# schematic.net
KiCad netlist of a schematic drawn in Altium Designer
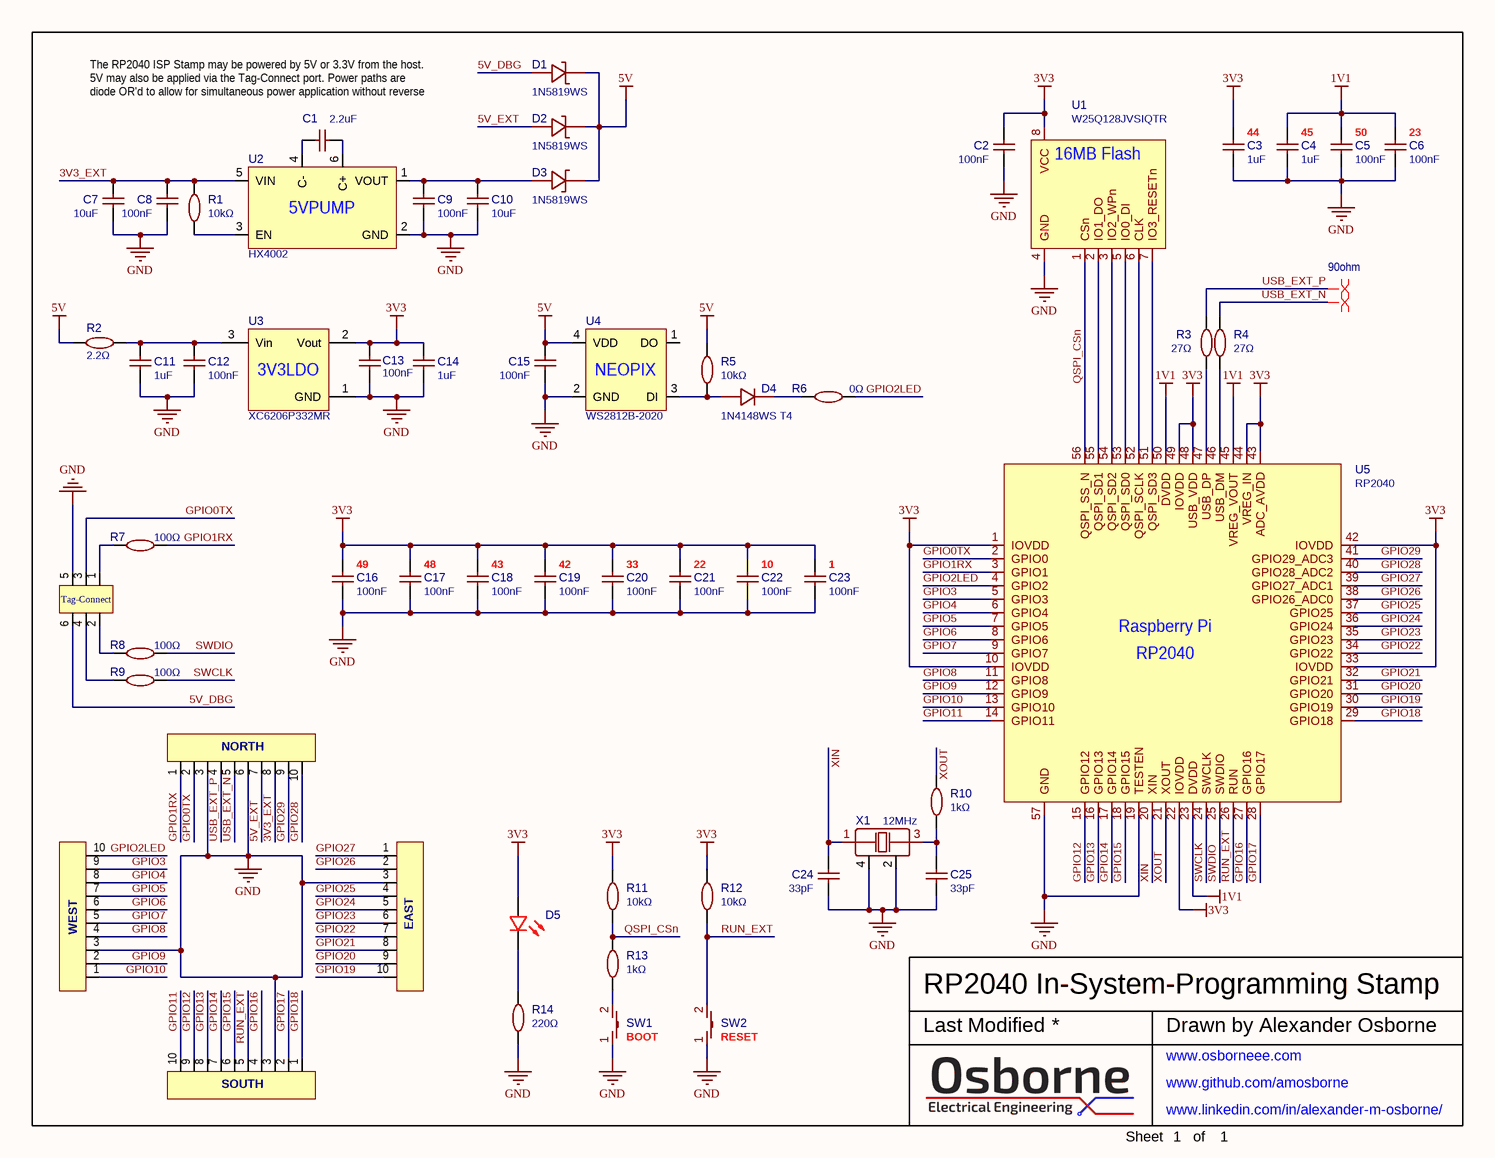
[diagram p0: schematic.SchDoc]

(export (version "E")
  (design (tool "Eeschema 10.0.6"))
  (components
    (comp (ref "C1")
      (value "2.2uF")
      (footprint "C0603")
      (description "16V 2.2uF X5R ±10% 0603  Multilayer Ceramic Capacitors MLCC - SMD/SMT ROHS")
      (fields
        (field (name "BOM_MANUFACTURER PART") "CL10A225KO8NNNC")
        (field (name "BOM_SUPPLIER PART") "C23630")
      )
      (libsource (lib "sch_library") (part "2.2uF"))
    )
    (comp (ref "C2")
      (value "100nF")
      (footprint "C0402")
      (description "16V 100nF X7R ±10% 0402  Multilayer Ceramic Capacitors MLCC - SMD/SMT ROHS")
      (fields
        (field (name "BOM_MANUFACTURER PART") "CL05B104KO5NNNC")
        (field (name "BOM_SUPPLIER PART") "C1525")
      )
      (libsource (lib "sch_library") (part "100nF"))
    )
    (comp (ref "C3")
      (value "1uF")
      (footprint "C0402")
      (description "25V 1uF X5R ±10% 0402  Multilayer Ceramic Capacitors MLCC - SMD/SMT ROHS")
      (fields
        (field (name "BOM_MANUFACTURER PART") "CL05A105KA5NQNC")
        (field (name "BOM_SUPPLIER PART") "C52923")
      )
      (libsource (lib "sch_library") (part "1uF"))
    )
    (comp (ref "C4")
      (value "1uF")
      (footprint "C0402")
      (description "25V 1uF X5R ±10% 0402  Multilayer Ceramic Capacitors MLCC - SMD/SMT ROHS")
      (fields
        (field (name "BOM_MANUFACTURER PART") "CL05A105KA5NQNC")
        (field (name "BOM_SUPPLIER PART") "C52923")
      )
      (libsource (lib "sch_library") (part "1uF"))
    )
    (comp (ref "C5")
      (value "100nF")
      (footprint "C0402")
      (description "16V 100nF X7R ±10% 0402  Multilayer Ceramic Capacitors MLCC - SMD/SMT ROHS")
      (fields
        (field (name "BOM_MANUFACTURER PART") "CL05B104KO5NNNC")
        (field (name "BOM_SUPPLIER PART") "C1525")
      )
      (libsource (lib "sch_library") (part "100nF"))
    )
    (comp (ref "C6")
      (value "100nF")
      (footprint "C0402")
      (description "16V 100nF X7R ±10% 0402  Multilayer Ceramic Capacitors MLCC - SMD/SMT ROHS")
      (fields
        (field (name "BOM_MANUFACTURER PART") "CL05B104KO5NNNC")
        (field (name "BOM_SUPPLIER PART") "C1525")
      )
      (libsource (lib "sch_library") (part "100nF"))
    )
    (comp (ref "C7")
      (value "10uF")
      (footprint "C0603")
      (description "X5R 25V ±20% 10uF 0603 Multilayer Ceramic Capacitors MLCC - SMD/SMT ROHS")
      (fields
        (field (name "BOM_MANUFACTURER PART") "CL10A106MA8NRNC")
        (field (name "BOM_SUPPLIER PART") "C96446")
      )
      (libsource (lib "sch_library") (part "10uF"))
    )
    (comp (ref "C8")
      (value "100nF")
      (footprint "C0402")
      (description "16V 100nF X7R ±10% 0402  Multilayer Ceramic Capacitors MLCC - SMD/SMT ROHS")
      (fields
        (field (name "BOM_MANUFACTURER PART") "CL05B104KO5NNNC")
        (field (name "BOM_SUPPLIER PART") "C1525")
      )
      (libsource (lib "sch_library") (part "100nF"))
    )
    (comp (ref "C9")
      (value "100nF")
      (footprint "C0402")
      (description "16V 100nF X7R ±10% 0402  Multilayer Ceramic Capacitors MLCC - SMD/SMT ROHS")
      (fields
        (field (name "BOM_MANUFACTURER PART") "CL05B104KO5NNNC")
        (field (name "BOM_SUPPLIER PART") "C1525")
      )
      (libsource (lib "sch_library") (part "100nF"))
    )
    (comp (ref "C10")
      (value "10uF")
      (footprint "C0603")
      (description "X5R 25V ±20% 10uF 0603 Multilayer Ceramic Capacitors MLCC - SMD/SMT ROHS")
      (fields
        (field (name "BOM_MANUFACTURER PART") "CL10A106MA8NRNC")
        (field (name "BOM_SUPPLIER PART") "C96446")
      )
      (libsource (lib "sch_library") (part "10uF"))
    )
    (comp (ref "C11")
      (value "1uF")
      (footprint "C0402")
      (description "25V 1uF X5R ±10% 0402  Multilayer Ceramic Capacitors MLCC - SMD/SMT ROHS")
      (fields
        (field (name "BOM_MANUFACTURER PART") "CL05A105KA5NQNC")
        (field (name "BOM_SUPPLIER PART") "C52923")
      )
      (libsource (lib "sch_library") (part "1uF"))
    )
    (comp (ref "C12")
      (value "100nF")
      (footprint "C0402")
      (description "16V 100nF X7R ±10% 0402  Multilayer Ceramic Capacitors MLCC - SMD/SMT ROHS")
      (fields
        (field (name "BOM_MANUFACTURER PART") "CL05B104KO5NNNC")
        (field (name "BOM_SUPPLIER PART") "C1525")
      )
      (libsource (lib "sch_library") (part "100nF"))
    )
    (comp (ref "C13")
      (value "100nF")
      (footprint "C0402")
      (description "16V 100nF X7R ±10% 0402  Multilayer Ceramic Capacitors MLCC - SMD/SMT ROHS")
      (fields
        (field (name "BOM_MANUFACTURER PART") "CL05B104KO5NNNC")
        (field (name "BOM_SUPPLIER PART") "C1525")
      )
      (libsource (lib "sch_library") (part "100nF"))
    )
    (comp (ref "C14")
      (value "1uF")
      (footprint "C0402")
      (description "25V 1uF X5R ±10% 0402  Multilayer Ceramic Capacitors MLCC - SMD/SMT ROHS")
      (fields
        (field (name "BOM_MANUFACTURER PART") "CL05A105KA5NQNC")
        (field (name "BOM_SUPPLIER PART") "C52923")
      )
      (libsource (lib "sch_library") (part "1uF"))
    )
    (comp (ref "C15")
      (value "100nF")
      (footprint "C0402")
      (description "16V 100nF X7R ±10% 0402  Multilayer Ceramic Capacitors MLCC - SMD/SMT ROHS")
      (fields
        (field (name "BOM_MANUFACTURER PART") "CL05B104KO5NNNC")
        (field (name "BOM_SUPPLIER PART") "C1525")
      )
      (libsource (lib "sch_library") (part "100nF"))
    )
    (comp (ref "C16")
      (value "100nF")
      (footprint "C0402")
      (description "16V 100nF X7R ±10% 0402  Multilayer Ceramic Capacitors MLCC - SMD/SMT ROHS")
      (fields
        (field (name "BOM_MANUFACTURER PART") "CL05B104KO5NNNC")
        (field (name "BOM_SUPPLIER PART") "C1525")
      )
      (libsource (lib "sch_library") (part "100nF"))
    )
    (comp (ref "C17")
      (value "100nF")
      (footprint "C0402")
      (description "16V 100nF X7R ±10% 0402  Multilayer Ceramic Capacitors MLCC - SMD/SMT ROHS")
      (fields
        (field (name "BOM_MANUFACTURER PART") "CL05B104KO5NNNC")
        (field (name "BOM_SUPPLIER PART") "C1525")
      )
      (libsource (lib "sch_library") (part "100nF"))
    )
    (comp (ref "C18")
      (value "100nF")
      (footprint "C0402")
      (description "16V 100nF X7R ±10% 0402  Multilayer Ceramic Capacitors MLCC - SMD/SMT ROHS")
      (fields
        (field (name "BOM_MANUFACTURER PART") "CL05B104KO5NNNC")
        (field (name "BOM_SUPPLIER PART") "C1525")
      )
      (libsource (lib "sch_library") (part "100nF"))
    )
    (comp (ref "C19")
      (value "100nF")
      (footprint "C0402")
      (description "16V 100nF X7R ±10% 0402  Multilayer Ceramic Capacitors MLCC - SMD/SMT ROHS")
      (fields
        (field (name "BOM_MANUFACTURER PART") "CL05B104KO5NNNC")
        (field (name "BOM_SUPPLIER PART") "C1525")
      )
      (libsource (lib "sch_library") (part "100nF"))
    )
    (comp (ref "C20")
      (value "100nF")
      (footprint "C0402")
      (description "16V 100nF X7R ±10% 0402  Multilayer Ceramic Capacitors MLCC - SMD/SMT ROHS")
      (fields
        (field (name "BOM_MANUFACTURER PART") "CL05B104KO5NNNC")
        (field (name "BOM_SUPPLIER PART") "C1525")
      )
      (libsource (lib "sch_library") (part "100nF"))
    )
    (comp (ref "C21")
      (value "100nF")
      (footprint "C0402")
      (description "16V 100nF X7R ±10% 0402  Multilayer Ceramic Capacitors MLCC - SMD/SMT ROHS")
      (fields
        (field (name "BOM_MANUFACTURER PART") "CL05B104KO5NNNC")
        (field (name "BOM_SUPPLIER PART") "C1525")
      )
      (libsource (lib "sch_library") (part "100nF"))
    )
    (comp (ref "C22")
      (value "100nF")
      (footprint "C0402")
      (description "16V 100nF X7R ±10% 0402  Multilayer Ceramic Capacitors MLCC - SMD/SMT ROHS")
      (fields
        (field (name "BOM_MANUFACTURER PART") "CL05B104KO5NNNC")
        (field (name "BOM_SUPPLIER PART") "C1525")
      )
      (libsource (lib "sch_library") (part "100nF"))
    )
    (comp (ref "C23")
      (value "100nF")
      (footprint "C0402")
      (description "16V 100nF X7R ±10% 0402  Multilayer Ceramic Capacitors MLCC - SMD/SMT ROHS")
      (fields
        (field (name "BOM_MANUFACTURER PART") "CL05B104KO5NNNC")
        (field (name "BOM_SUPPLIER PART") "C1525")
      )
      (libsource (lib "sch_library") (part "100nF"))
    )
    (comp (ref "C24")
      (value "33pF")
      (footprint "C0402")
      (description "50V 33pF C0G ±5% 0402  Multilayer Ceramic Capacitors MLCC - SMD/SMT ROHS")
      (fields
        (field (name "BOM_MANUFACTURER PART") "0402CG330J500NT")
        (field (name "BOM_SUPPLIER PART") "C1562")
      )
      (libsource (lib "sch_library") (part "33pF"))
    )
    (comp (ref "C25")
      (value "33pF")
      (footprint "C0402")
      (description "50V 33pF C0G ±5% 0402  Multilayer Ceramic Capacitors MLCC - SMD/SMT ROHS")
      (fields
        (field (name "BOM_MANUFACTURER PART") "0402CG330J500NT")
        (field (name "BOM_SUPPLIER PART") "C1562")
      )
      (libsource (lib "sch_library") (part "33pF"))
    )
    (comp (ref "D1")
      (value "1N5819WS")
      (footprint "SOD-323_L1.8-W1.3-LS2.5-RD")
      (description "40V 600mV@1A 1A SOD-323  Schottky Barrier Diodes (SBD) ROHS")
      (fields (field (name "BOM_SUPPLIER PART") "C191023") (field (name "CONTRIBUTOR") "LCSC"))
      (libsource (lib "sch_library") (part "1N5819WS"))
    )
    (comp (ref "D2")
      (value "1N5819WS")
      (footprint "SOD-323_L1.8-W1.3-LS2.5-RD")
      (description "40V 600mV@1A 1A SOD-323  Schottky Barrier Diodes (SBD) ROHS")
      (fields (field (name "BOM_SUPPLIER PART") "C191023") (field (name "CONTRIBUTOR") "LCSC"))
      (libsource (lib "sch_library") (part "1N5819WS"))
    )
    (comp (ref "D3")
      (value "1N5819WS")
      (footprint "SOD-323_L1.8-W1.3-LS2.5-RD")
      (description "40V 600mV@1A 1A SOD-323  Schottky Barrier Diodes (SBD) ROHS")
      (fields (field (name "BOM_SUPPLIER PART") "C191023") (field (name "CONTRIBUTOR") "LCSC"))
      (libsource (lib "sch_library") (part "1N5819WS"))
    )
    (comp (ref "D4")
      (value "1N4148WS T4")
      (footprint "SOD-323_L1.8-W1.3-LS2.5-RD")
      (description "100V +150℃@(Tj) 200mW Single 1.25V@150mA 4ns 1μA@75V 150mA SOD-323  Switching Diode ROHS")
      (fields (field (name "BOM_SUPPLIER PART") "C2128"))
      (libsource (lib "sch_library") (part "1N4148WS T4"))
    )
    (comp (ref "D5")
      (value "19-217/GHC-YR1S2/3T")
      (footprint "LED0603-R-RD")
      (fields (field (name "BOM_SUPPLIER PART") "C72043"))
      (libsource (lib "sch_library") (part "19-217/GHC-YR1S2/3T"))
    )
    (comp (ref "EAST")
      (value "STAMPEDGE")
      (footprint "CASTELLATIONS")
      (description "RP2040 ISP Stamp Castellations")
      (libsource (lib "") (part "STAMPEDGE_3"))
    )
    (comp (ref "J1")
      (value "TC2030-IDC-NL")
      (footprint "TC2030-IDC-NL")
      (description "Tag-Connect 6-Pin No Legs")
      (libsource (lib "sch_library") (part "TC2030-IDC-NL"))
    )
    (comp (ref "NORTH")
      (value "STAMPEDGE")
      (footprint "CASTELLATIONS")
      (description "RP2040 ISP Stamp Castellations")
      (libsource (lib "") (part "STAMPEDGE_1"))
    )
    (comp (ref "R1")
      (value "10kΩ")
      (footprint "R0402")
      (fields
        (field (name "BOM_MANUFACTURER PART") "0402WGF1002TCE")
        (field (name "BOM_SUPPLIER PART") "C25744")
      )
      (libsource (lib "sch_library") (part "10kΩ"))
    )
    (comp (ref "R2")
      (value "2.2Ω")
      (footprint "R0603")
      (fields
        (field (name "BOM_MANUFACTURER PART") "0603WAF220KT5E")
        (field (name "BOM_SUPPLIER PART") "C22939")
      )
      (libsource (lib "sch_library") (part "2.2Ω"))
    )
    (comp (ref "R3")
      (value "27Ω")
      (footprint "R0603")
      (fields
        (field (name "BOM_MANUFACTURER PART") "0603WAF270JT5E")
        (field (name "BOM_SUPPLIER PART") "C25190")
      )
      (libsource (lib "sch_library") (part "27Ω"))
    )
    (comp (ref "R4")
      (value "27Ω")
      (footprint "R0603")
      (fields
        (field (name "BOM_MANUFACTURER PART") "0603WAF270JT5E")
        (field (name "BOM_SUPPLIER PART") "C25190")
      )
      (libsource (lib "sch_library") (part "27Ω"))
    )
    (comp (ref "R5")
      (value "10kΩ")
      (footprint "R0402")
      (fields
        (field (name "BOM_MANUFACTURER PART") "0402WGF1002TCE")
        (field (name "BOM_SUPPLIER PART") "C25744")
      )
      (libsource (lib "sch_library") (part "10kΩ"))
    )
    (comp (ref "R6")
      (value "0Ω")
      (footprint "R0805")
      (fields
        (field (name "BOM_MANUFACTURER PART") "0805W8F0000T5E")
        (field (name "BOM_SUPPLIER PART") "C17477")
      )
      (libsource (lib "sch_library") (part "0Ω"))
    )
    (comp (ref "R7")
      (value "100Ω")
      (footprint "R0402")
      (fields
        (field (name "BOM_MANUFACTURER PART") "0402WGF1000TCE")
        (field (name "BOM_SUPPLIER PART") "C25076")
      )
      (libsource (lib "sch_library") (part "100Ω"))
    )
    (comp (ref "R8")
      (value "100Ω")
      (footprint "R0402")
      (fields
        (field (name "BOM_MANUFACTURER PART") "0402WGF1000TCE")
        (field (name "BOM_SUPPLIER PART") "C25076")
      )
      (libsource (lib "sch_library") (part "100Ω"))
    )
    (comp (ref "R9")
      (value "100Ω")
      (footprint "R0402")
      (fields
        (field (name "BOM_MANUFACTURER PART") "0402WGF1000TCE")
        (field (name "BOM_SUPPLIER PART") "C25076")
      )
      (libsource (lib "sch_library") (part "100Ω"))
    )
    (comp (ref "R10")
      (value "1kΩ")
      (footprint "R0402")
      (fields
        (field (name "BOM_MANUFACTURER PART") "0402WGF1001TCE")
        (field (name "BOM_SUPPLIER PART") "C11702")
      )
      (libsource (lib "sch_library") (part "1kΩ"))
    )
    (comp (ref "R11")
      (value "10kΩ")
      (footprint "R0402")
      (fields
        (field (name "BOM_MANUFACTURER PART") "0402WGF1002TCE")
        (field (name "BOM_SUPPLIER PART") "C25744")
      )
      (libsource (lib "sch_library") (part "10kΩ"))
    )
    (comp (ref "R12")
      (value "10kΩ")
      (footprint "R0402")
      (fields
        (field (name "BOM_MANUFACTURER PART") "0402WGF1002TCE")
        (field (name "BOM_SUPPLIER PART") "C25744")
      )
      (libsource (lib "sch_library") (part "10kΩ"))
    )
    (comp (ref "R13")
      (value "1kΩ")
      (footprint "R0402")
      (fields
        (field (name "BOM_MANUFACTURER PART") "0402WGF1001TCE")
        (field (name "BOM_SUPPLIER PART") "C11702")
      )
      (libsource (lib "sch_library") (part "1kΩ"))
    )
    (comp (ref "R14")
      (value "220Ω")
      (footprint "R0402")
      (fields
        (field (name "BOM_MANUFACTURER PART") "0402WGF2200TCE")
        (field (name "BOM_SUPPLIER PART") "C25091")
      )
      (libsource (lib "sch_library") (part "220Ω"))
    )
    (comp (ref "SOUTH")
      (value "STAMPEDGE")
      (footprint "CASTELLATIONS")
      (description "RP2040 ISP Stamp Castellations")
      (libsource (lib "sch_library") (part "STAMPEDGE"))
    )
    (comp (ref "SW1")
      (value "B3U-1000P")
      (footprint "KEY-SMD_B3U-1000PM")
      (description "2.5mm 1.6mm Round Button 50mA Brick nogging 3mm SPST 12V SMD,3x2.5x1.6mm  Tactile Switches ROHS")
      (fields (field (name "BOM_SUPPLIER PART") "C231329") (field (name "CONTRIBUTOR") "LCSC"))
      (libsource (lib "sch_library") (part "B3U-1000P"))
    )
    (comp (ref "SW2")
      (value "B3U-1000P")
      (footprint "KEY-SMD_B3U-1000PM")
      (description "2.5mm 1.6mm Round Button 50mA Brick nogging 3mm SPST 12V SMD,3x2.5x1.6mm  Tactile Switches ROHS")
      (fields (field (name "BOM_SUPPLIER PART") "C231329") (field (name "CONTRIBUTOR") "LCSC"))
      (libsource (lib "sch_library") (part "B3U-1000P"))
    )
    (comp (ref "U1")
      (value "W25Q128JVSIQTR")
      (footprint "SOIC-8_L5.3-W5.3-P1.27-LS8.0-BL")
      (description "SOIC-8_208mil  NOR FLASH ROHS")
      (fields (field (name "BOM_SUPPLIER PART") "C97521"))
      (libsource (lib "sch_library") (part "W25Q128JVSIQTR"))
    )
    (comp (ref "U2")
      (value "HX4002")
      (footprint "SOT-23-6_L2.9-W1.6-P0.95-LS2.8-BR")
      (description "NO Charge pump 1 5V 2.7V~5.5V 250mA 1.2MHz SOT-23-6  DC-DC Converters ROHS")
      (fields (field (name "BOM_SUPPLIER PART") "C172354") (field (name "CONTRIBUTOR") "LCSC"))
      (libsource (lib "sch_library") (part "HX4002"))
    )
    (comp (ref "U3")
      (value "XC6206P332MR")
      (footprint "SOT-23-3_L2.9-W1.6-P1.90-LS2.8-BR")
      (description "200mA 680mV@(100mA) Fixed 3.3V~3.3V Positive 1 6V SOT-23-3L  Linear Voltage Regulators (LDO) ROHS")
      (fields (field (name "BOM_SUPPLIER PART") "C5446"))
      (libsource (lib "sch_library") (part "XC6206P332MR"))
    )
    (comp (ref "U4")
      (value "WS2812B-2020")
      (footprint "LED-SMD_4P-L2.0-W2.0-TL_WS2812B-2020")
      (description "5mA 5.3V -25℃~+85℃ RGB SMD,2x2mm  Light Emitting Diodes (LED) ROHS")
      (fields (field (name "BOM_SUPPLIER PART") "C965555") (field (name "CONTRIBUTOR") "LCSC"))
      (libsource (lib "sch_library") (part "WS2812B-2020"))
    )
    (comp (ref "U5")
      (value "RP2040")
      (footprint "LQFN-56_L7.0-W7.0-P0.4-EP")
      (fields (field (name "BOM_SUPPLIER PART") "C2040") (field (name "CONTRIBUTOR") "LCSC"))
      (libsource (lib "sch_library") (part "RP2040"))
    )
    (comp (ref "WEST")
      (value "STAMPEDGE")
      (footprint "CASTELLATIONS")
      (description "RP2040 ISP Stamp Castellations")
      (libsource (lib "") (part "STAMPEDGE_2"))
    )
    (comp (ref "X1")
      (value "12MHz")
      (footprint "OSC-SMD_4P-L3.2-W2.5-BL")
      (description "12MHz SMD Crystal Resonator 20pF ±10ppm ±30ppm -40℃~+85℃ SMD3225-4P  Crystals ROHS")
      (fields
        (field (name "BOM_MANUFACTURER PART") "X322512MSB4SI")
        (field (name "BOM_SUPPLIER PART") "C9002")
      )
      (libsource (lib "sch_library") (part "12MHz"))
    )
  )
  (nets
    (net (code "1") (name "/3V3_EXT") (class "Default")
      (node (ref "C7") (pin "2") (pinfunction "2_2") (pintype "passive"))
      (node (ref "C8") (pin "2") (pinfunction "2_2") (pintype "passive"))
      (node (ref "NORTH") (pin "8") (pintype "passive"))
      (node (ref "R1") (pin "2") (pinfunction "2_2") (pintype "passive"))
      (node (ref "U2") (pin "5") (pinfunction "VIN_5") (pintype "passive"))
    )
    (net (code "2") (name "/5V_DBG") (class "Default")
      (node (ref "D1") (pin "2") (pinfunction "A_2") (pintype "passive"))
      (node (ref "J1") (pin "6") (pintype "passive"))
    )
    (net (code "3") (name "/5V_EXT") (class "Default")
      (node (ref "D2") (pin "2") (pinfunction "A_2") (pintype "passive"))
      (node (ref "NORTH") (pin "7") (pintype "passive"))
    )
    (net (code "4") (name "/GPIO0TX") (class "Default")
      (node (ref "J1") (pin "3") (pintype "passive"))
      (node (ref "NORTH") (pin "2") (pintype "passive"))
      (node (ref "U5") (pin "2") (pinfunction "GPIO0_2") (pintype "passive"))
    )
    (net (code "5") (name "/GPIO1RX") (class "Default")
      (node (ref "NORTH") (pin "1") (pintype "passive"))
      (node (ref "R7") (pin "1") (pinfunction "1_1") (pintype "passive"))
      (node (ref "U5") (pin "3") (pinfunction "GPIO1_3") (pintype "passive"))
    )
    (net (code "6") (name "/GPIO2LED") (class "Default")
      (node (ref "R6") (pin "2") (pinfunction "2_2") (pintype "passive"))
      (node (ref "U5") (pin "4") (pinfunction "GPIO2_4") (pintype "passive"))
      (node (ref "WEST") (pin "10") (pintype "passive"))
    )
    (net (code "7") (name "/GPIO3") (class "Default")
      (node (ref "U5") (pin "5") (pinfunction "GPIO3_5") (pintype "passive"))
      (node (ref "WEST") (pin "9") (pintype "passive"))
    )
    (net (code "8") (name "/GPIO4") (class "Default")
      (node (ref "U5") (pin "6") (pinfunction "GPIO4_6") (pintype "passive"))
      (node (ref "WEST") (pin "8") (pintype "passive"))
    )
    (net (code "9") (name "/GPIO5") (class "Default")
      (node (ref "U5") (pin "7") (pinfunction "GPIO5_7") (pintype "passive"))
      (node (ref "WEST") (pin "7") (pintype "passive"))
    )
    (net (code "10") (name "/GPIO6") (class "Default")
      (node (ref "U5") (pin "8") (pinfunction "GPIO6_8") (pintype "passive"))
      (node (ref "WEST") (pin "6") (pintype "passive"))
    )
    (net (code "11") (name "/GPIO7") (class "Default")
      (node (ref "U5") (pin "9") (pinfunction "GPIO7_9") (pintype "passive"))
      (node (ref "WEST") (pin "5") (pintype "passive"))
    )
    (net (code "12") (name "/GPIO8") (class "Default")
      (node (ref "U5") (pin "11") (pinfunction "GPIO8_11") (pintype "passive"))
      (node (ref "WEST") (pin "4") (pintype "passive"))
    )
    (net (code "13") (name "/GPIO9") (class "Default")
      (node (ref "U5") (pin "12") (pinfunction "GPIO9_12") (pintype "passive"))
      (node (ref "WEST") (pin "2") (pintype "passive"))
    )
    (net (code "14") (name "/GPIO10") (class "Default")
      (node (ref "U5") (pin "13") (pinfunction "GPIO10_13") (pintype "passive"))
      (node (ref "WEST") (pin "1") (pintype "passive"))
    )
    (net (code "15") (name "/GPIO11") (class "Default")
      (node (ref "SOUTH") (pin "10") (pintype "passive"))
      (node (ref "U5") (pin "14") (pinfunction "GPIO11_14") (pintype "passive"))
    )
    (net (code "16") (name "/GPIO12") (class "Default")
      (node (ref "SOUTH") (pin "9") (pintype "passive"))
      (node (ref "U5") (pin "15") (pinfunction "GPIO12_15") (pintype "passive"))
    )
    (net (code "17") (name "/GPIO13") (class "Default")
      (node (ref "SOUTH") (pin "8") (pintype "passive"))
      (node (ref "U5") (pin "16") (pinfunction "GPIO13_16") (pintype "passive"))
    )
    (net (code "18") (name "/GPIO14") (class "Default")
      (node (ref "SOUTH") (pin "7") (pintype "passive"))
      (node (ref "U5") (pin "17") (pinfunction "GPIO14_17") (pintype "passive"))
    )
    (net (code "19") (name "/GPIO15") (class "Default")
      (node (ref "SOUTH") (pin "6") (pintype "passive"))
      (node (ref "U5") (pin "18") (pinfunction "GPIO15_18") (pintype "passive"))
    )
    (net (code "20") (name "/GPIO16") (class "Default")
      (node (ref "SOUTH") (pin "4") (pintype "passive"))
      (node (ref "U5") (pin "27") (pinfunction "GPIO16_27") (pintype "passive"))
    )
    (net (code "21") (name "/GPIO17") (class "Default")
      (node (ref "SOUTH") (pin "2") (pintype "passive"))
      (node (ref "U5") (pin "28") (pinfunction "GPIO17_28") (pintype "passive"))
    )
    (net (code "22") (name "/GPIO18") (class "Default")
      (node (ref "SOUTH") (pin "1") (pintype "passive"))
      (node (ref "U5") (pin "29") (pinfunction "GPIO18_29") (pintype "passive"))
    )
    (net (code "23") (name "/GPIO19") (class "Default")
      (node (ref "EAST") (pin "10") (pintype "passive"))
      (node (ref "U5") (pin "30") (pinfunction "GPIO19_30") (pintype "passive"))
    )
    (net (code "24") (name "/GPIO20") (class "Default")
      (node (ref "EAST") (pin "9") (pintype "passive"))
      (node (ref "U5") (pin "31") (pinfunction "GPIO20_31") (pintype "passive"))
    )
    (net (code "25") (name "/GPIO21") (class "Default")
      (node (ref "EAST") (pin "8") (pintype "passive"))
      (node (ref "U5") (pin "32") (pinfunction "GPIO21_32") (pintype "passive"))
    )
    (net (code "26") (name "/GPIO22") (class "Default")
      (node (ref "EAST") (pin "7") (pintype "passive"))
      (node (ref "U5") (pin "34") (pinfunction "GPIO22_34") (pintype "passive"))
    )
    (net (code "27") (name "/GPIO23") (class "Default")
      (node (ref "EAST") (pin "6") (pintype "passive"))
      (node (ref "U5") (pin "35") (pinfunction "GPIO23_35") (pintype "passive"))
    )
    (net (code "28") (name "/GPIO24") (class "Default")
      (node (ref "EAST") (pin "5") (pintype "passive"))
      (node (ref "U5") (pin "36") (pinfunction "GPIO24_36") (pintype "passive"))
    )
    (net (code "29") (name "/GPIO25") (class "Default")
      (node (ref "EAST") (pin "4") (pintype "passive"))
      (node (ref "U5") (pin "37") (pinfunction "GPIO25_37") (pintype "passive"))
    )
    (net (code "30") (name "/GPIO26") (class "Default")
      (node (ref "EAST") (pin "2") (pintype "passive"))
      (node (ref "U5") (pin "38") (pinfunction "GPIO26_ADC0_38") (pintype "passive"))
    )
    (net (code "31") (name "/GPIO27") (class "Default")
      (node (ref "EAST") (pin "1") (pintype "passive"))
      (node (ref "U5") (pin "39") (pinfunction "GPIO27_ADC1_39") (pintype "passive"))
    )
    (net (code "32") (name "/GPIO28") (class "Default")
      (node (ref "NORTH") (pin "10") (pintype "passive"))
      (node (ref "U5") (pin "40") (pinfunction "GPIO28_ADC2_40") (pintype "passive"))
    )
    (net (code "33") (name "/GPIO29") (class "Default")
      (node (ref "NORTH") (pin "9") (pintype "passive"))
      (node (ref "U5") (pin "41") (pinfunction "GPIO29_ADC3_41") (pintype "passive"))
    )
    (net (code "34") (name "/QSPI_CSn") (class "Default")
      (node (ref "R11") (pin "1") (pinfunction "1_1") (pintype "passive"))
      (node (ref "R13") (pin "2") (pinfunction "2_2") (pintype "passive"))
      (node (ref "U1") (pin "1") (pinfunction "CSn_1") (pintype "passive"))
      (node (ref "U5") (pin "56") (pinfunction "QSPI_SS_N_56") (pintype "passive"))
    )
    (net (code "35") (name "/RUN_EXT") (class "Default")
      (node (ref "R12") (pin "1") (pinfunction "1_1") (pintype "passive"))
      (node (ref "SOUTH") (pin "5") (pintype "passive"))
      (node (ref "SW2") (pin "2") (pinfunction "2_2") (pintype "passive"))
      (node (ref "U5") (pin "26") (pinfunction "RUN_26") (pintype "passive"))
    )
    (net (code "36") (name "/SWCLK") (class "Default")
      (node (ref "R9") (pin "1") (pinfunction "1_1") (pintype "passive"))
      (node (ref "U5") (pin "24") (pinfunction "SWCLK_24") (pintype "passive"))
    )
    (net (code "37") (name "/SWDIO") (class "Default")
      (node (ref "R8") (pin "1") (pinfunction "1_1") (pintype "passive"))
      (node (ref "U5") (pin "25") (pinfunction "SWDIO_25") (pintype "passive"))
    )
    (net (code "38") (name "/USB_EXT_N") (class "Default")
      (node (ref "NORTH") (pin "5") (pintype "passive"))
      (node (ref "R4") (pin "2") (pinfunction "2_2") (pintype "passive"))
    )
    (net (code "39") (name "/USB_EXT_P") (class "Default")
      (node (ref "NORTH") (pin "4") (pintype "passive"))
      (node (ref "R3") (pin "2") (pinfunction "2_2") (pintype "passive"))
    )
    (net (code "40") (name "/XIN") (class "Default")
      (node (ref "C24") (pin "2") (pinfunction "2_2") (pintype "passive"))
      (node (ref "U5") (pin "20") (pinfunction "XIN_20") (pintype "passive"))
      (node (ref "X1") (pin "1") (pinfunction "OSC1_1") (pintype "passive"))
    )
    (net (code "41") (name "/XOUT") (class "Default")
      (node (ref "R10") (pin "1") (pinfunction "1_1") (pintype "passive"))
      (node (ref "U5") (pin "21") (pinfunction "XOUT_21") (pintype "passive"))
    )
    (net (code "42") (name "1V1") (class "Default")
      (node (ref "C4") (pin "2") (pinfunction "2_2") (pintype "passive"))
      (node (ref "C5") (pin "2") (pinfunction "2_2") (pintype "passive"))
      (node (ref "C6") (pin "2") (pinfunction "2_2") (pintype "passive"))
      (node (ref "U5") (pin "23") (pinfunction "DVDD_23") (pintype "passive"))
      (node (ref "U5") (pin "45") (pinfunction "VREG_VOUT_45") (pintype "passive"))
      (node (ref "U5") (pin "50") (pinfunction "DVDD_50") (pintype "passive"))
    )
    (net (code "43") (name "3V3") (class "Default")
      (node (ref "C13") (pin "2") (pinfunction "2_2") (pintype "passive"))
      (node (ref "C14") (pin "2") (pinfunction "2_2") (pintype "passive"))
      (node (ref "C16") (pin "2") (pinfunction "2_2") (pintype "passive"))
      (node (ref "C17") (pin "2") (pinfunction "2_2") (pintype "passive"))
      (node (ref "C18") (pin "2") (pinfunction "2_2") (pintype "passive"))
      (node (ref "C19") (pin "2") (pinfunction "2_2") (pintype "passive"))
      (node (ref "C2") (pin "2") (pinfunction "2_2") (pintype "passive"))
      (node (ref "C20") (pin "2") (pinfunction "2_2") (pintype "passive"))
      (node (ref "C21") (pin "2") (pinfunction "2_2") (pintype "passive"))
      (node (ref "C22") (pin "2") (pinfunction "2_2") (pintype "passive"))
      (node (ref "C23") (pin "2") (pinfunction "2_2") (pintype "passive"))
      (node (ref "C3") (pin "2") (pinfunction "2_2") (pintype "passive"))
      (node (ref "D5") (pin "1") (pinfunction "A_1") (pintype "passive"))
      (node (ref "R11") (pin "2") (pinfunction "2_2") (pintype "passive"))
      (node (ref "R12") (pin "2") (pinfunction "2_2") (pintype "passive"))
      (node (ref "U1") (pin "8") (pinfunction "VCC_8") (pintype "passive"))
      (node (ref "U3") (pin "2") (pinfunction "Vout_2") (pintype "passive"))
      (node (ref "U5") (pin "1") (pinfunction "IOVDD_1") (pintype "passive"))
      (node (ref "U5") (pin "10") (pinfunction "IOVDD_10") (pintype "passive"))
      (node (ref "U5") (pin "22") (pinfunction "IOVDD_22") (pintype "passive"))
      (node (ref "U5") (pin "33") (pinfunction "IOVDD_33") (pintype "passive"))
      (node (ref "U5") (pin "42") (pinfunction "IOVDD_42") (pintype "passive"))
      (node (ref "U5") (pin "43") (pinfunction "ADC_AVDD_43") (pintype "passive"))
      (node (ref "U5") (pin "44") (pinfunction "VREG_IN_44") (pintype "passive"))
      (node (ref "U5") (pin "48") (pinfunction "USB_VDD_48") (pintype "passive"))
      (node (ref "U5") (pin "49") (pinfunction "IOVDD_49") (pintype "passive"))
    )
    (net (code "44") (name "5V") (class "Default")
      (node (ref "C15") (pin "2") (pinfunction "2_2") (pintype "passive"))
      (node (ref "D1") (pin "1") (pinfunction "C_1") (pintype "passive"))
      (node (ref "D2") (pin "1") (pinfunction "C_1") (pintype "passive"))
      (node (ref "D3") (pin "1") (pinfunction "C_1") (pintype "passive"))
      (node (ref "R2") (pin "1") (pinfunction "1_1") (pintype "passive"))
      (node (ref "R5") (pin "2") (pinfunction "2_2") (pintype "passive"))
      (node (ref "U4") (pin "4") (pinfunction "VDD_4") (pintype "passive"))
    )
    (net (code "45") (name "GND") (class "Default")
      (node (ref "C10") (pin "1") (pinfunction "1_1") (pintype "passive"))
      (node (ref "C11") (pin "1") (pinfunction "1_1") (pintype "passive"))
      (node (ref "C12") (pin "1") (pinfunction "1_1") (pintype "passive"))
      (node (ref "C13") (pin "1") (pinfunction "1_1") (pintype "passive"))
      (node (ref "C14") (pin "1") (pinfunction "1_1") (pintype "passive"))
      (node (ref "C15") (pin "1") (pinfunction "1_1") (pintype "passive"))
      (node (ref "C16") (pin "1") (pinfunction "1_1") (pintype "passive"))
      (node (ref "C17") (pin "1") (pinfunction "1_1") (pintype "passive"))
      (node (ref "C18") (pin "1") (pinfunction "1_1") (pintype "passive"))
      (node (ref "C19") (pin "1") (pinfunction "1_1") (pintype "passive"))
      (node (ref "C2") (pin "1") (pinfunction "1_1") (pintype "passive"))
      (node (ref "C20") (pin "1") (pinfunction "1_1") (pintype "passive"))
      (node (ref "C21") (pin "1") (pinfunction "1_1") (pintype "passive"))
      (node (ref "C22") (pin "1") (pinfunction "1_1") (pintype "passive"))
      (node (ref "C23") (pin "1") (pinfunction "1_1") (pintype "passive"))
      (node (ref "C24") (pin "1") (pinfunction "1_1") (pintype "passive"))
      (node (ref "C25") (pin "1") (pinfunction "1_1") (pintype "passive"))
      (node (ref "C3") (pin "1") (pinfunction "1_1") (pintype "passive"))
      (node (ref "C4") (pin "1") (pinfunction "1_1") (pintype "passive"))
      (node (ref "C5") (pin "1") (pinfunction "1_1") (pintype "passive"))
      (node (ref "C6") (pin "1") (pinfunction "1_1") (pintype "passive"))
      (node (ref "C7") (pin "1") (pinfunction "1_1") (pintype "passive"))
      (node (ref "C8") (pin "1") (pinfunction "1_1") (pintype "passive"))
      (node (ref "C9") (pin "1") (pinfunction "1_1") (pintype "passive"))
      (node (ref "EAST") (pin "3") (pintype "passive"))
      (node (ref "J1") (pin "5") (pintype "passive"))
      (node (ref "NORTH") (pin "3") (pintype "passive"))
      (node (ref "NORTH") (pin "6") (pintype "passive"))
      (node (ref "R14") (pin "1") (pinfunction "1_1") (pintype "passive"))
      (node (ref "SOUTH") (pin "3") (pintype "passive"))
      (node (ref "SW1") (pin "1") (pinfunction "1_1") (pintype "passive"))
      (node (ref "SW2") (pin "1") (pinfunction "1_1") (pintype "passive"))
      (node (ref "U1") (pin "4") (pinfunction "GND_4") (pintype "passive"))
      (node (ref "U2") (pin "2") (pinfunction "GND_2") (pintype "passive"))
      (node (ref "U3") (pin "1") (pinfunction "GND_1") (pintype "passive"))
      (node (ref "U4") (pin "2") (pinfunction "GND_2") (pintype "passive"))
      (node (ref "U5") (pin "19") (pinfunction "TESTEN_19") (pintype "passive"))
      (node (ref "U5") (pin "57") (pinfunction "GND_57") (pintype "passive"))
      (node (ref "WEST") (pin "3") (pintype "passive"))
      (node (ref "X1") (pin "2") (pinfunction "GND_2") (pintype "passive"))
      (node (ref "X1") (pin "4") (pinfunction "GND_4") (pintype "passive"))
    )
    (net (code "46") (name "Net-(D3-A)") (class "Default")
      (node (ref "C10") (pin "2") (pinfunction "2_2") (pintype "passive"))
      (node (ref "C9") (pin "2") (pinfunction "2_2") (pintype "passive"))
      (node (ref "D3") (pin "2") (pinfunction "A_2") (pintype "passive"))
      (node (ref "U2") (pin "1") (pinfunction "VOUT_1") (pintype "passive"))
    )
    (net (code "47") (name "Net-(D4-A)") (class "Default")
      (node (ref "D4") (pin "2") (pinfunction "A_2") (pintype "passive"))
      (node (ref "R5") (pin "1") (pinfunction "1_1") (pintype "passive"))
      (node (ref "U4") (pin "3") (pinfunction "DI_3") (pintype "passive"))
    )
    (net (code "48") (name "Net-(D4-K)") (class "Default")
      (node (ref "D4") (pin "1") (pinfunction "K_1") (pintype "passive"))
      (node (ref "R6") (pin "1") (pinfunction "1_1") (pintype "passive"))
    )
    (net (code "49") (name "Net-(D5-C)") (class "Default")
      (node (ref "D5") (pin "2") (pinfunction "C_2") (pintype "passive"))
      (node (ref "R14") (pin "2") (pinfunction "2_2") (pintype "passive"))
    )
    (net (code "50") (name "Net-(J1-Pad1)") (class "Default")
      (node (ref "J1") (pin "1") (pintype "passive"))
      (node (ref "R7") (pin "2") (pinfunction "2_2") (pintype "passive"))
    )
    (net (code "51") (name "Net-(J1-Pad2)") (class "Default")
      (node (ref "J1") (pin "2") (pintype "passive"))
      (node (ref "R8") (pin "2") (pinfunction "2_2") (pintype "passive"))
    )
    (net (code "52") (name "Net-(J1-Pad4)") (class "Default")
      (node (ref "J1") (pin "4") (pintype "passive"))
      (node (ref "R9") (pin "2") (pinfunction "2_2") (pintype "passive"))
    )
    (net (code "53") (name "Net-(R13-Pad1)") (class "Default")
      (node (ref "R13") (pin "1") (pinfunction "1_1") (pintype "passive"))
      (node (ref "SW1") (pin "2") (pinfunction "2_2") (pintype "passive"))
    )
    (net (code "54") (name "Net-(U1-CLK)") (class "Default")
      (node (ref "U1") (pin "6") (pinfunction "CLK_6") (pintype "passive"))
      (node (ref "U5") (pin "52") (pinfunction "QSPI_SCLK_52") (pintype "passive"))
    )
    (net (code "55") (name "Net-(U1-IO0_DI)") (class "Default")
      (node (ref "U1") (pin "5") (pinfunction "IO0_DI_5") (pintype "passive"))
      (node (ref "U5") (pin "53") (pinfunction "QSPI_SD0_53") (pintype "passive"))
    )
    (net (code "56") (name "Net-(U1-IO1_DO)") (class "Default")
      (node (ref "U1") (pin "2") (pinfunction "IO1_DO_2") (pintype "passive"))
      (node (ref "U5") (pin "55") (pinfunction "QSPI_SD1_55") (pintype "passive"))
    )
    (net (code "57") (name "Net-(U1-IO2_WPn)") (class "Default")
      (node (ref "U1") (pin "3") (pinfunction "IO2_WPn_3") (pintype "passive"))
      (node (ref "U5") (pin "54") (pinfunction "QSPI_SD2_54") (pintype "passive"))
    )
    (net (code "58") (name "Net-(U1-IO3_RESETn)") (class "Default")
      (node (ref "U1") (pin "7") (pinfunction "IO3_RESETn_7") (pintype "passive"))
      (node (ref "U5") (pin "51") (pinfunction "QSPI_SD3_51") (pintype "passive"))
    )
    (net (code "59") (name "Net-(U2-C+)") (class "Default")
      (node (ref "C1") (pin "1") (pinfunction "1_1") (pintype "passive"))
      (node (ref "U2") (pin "6") (pinfunction "C+_6") (pintype "passive"))
    )
    (net (code "60") (name "Net-(U2-C-)") (class "Default")
      (node (ref "C1") (pin "2") (pinfunction "2_2") (pintype "passive"))
      (node (ref "U2") (pin "4") (pinfunction "C-_4") (pintype "passive"))
    )
    (net (code "61") (name "Net-(U2-EN)") (class "Default")
      (node (ref "R1") (pin "1") (pinfunction "1_1") (pintype "passive"))
      (node (ref "U2") (pin "3") (pinfunction "EN_3") (pintype "passive"))
    )
    (net (code "62") (name "Net-(U3-Vin)") (class "Default")
      (node (ref "C11") (pin "2") (pinfunction "2_2") (pintype "passive"))
      (node (ref "C12") (pin "2") (pinfunction "2_2") (pintype "passive"))
      (node (ref "R2") (pin "2") (pinfunction "2_2") (pintype "passive"))
      (node (ref "U3") (pin "3") (pinfunction "Vin_3") (pintype "passive"))
    )
    (net (code "63") (name "Net-(U5-USB_DM)") (class "Default")
      (node (ref "R4") (pin "1") (pinfunction "1_1") (pintype "passive"))
      (node (ref "U5") (pin "46") (pinfunction "USB_DM_46") (pintype "passive"))
    )
    (net (code "64") (name "Net-(U5-USB_DP)") (class "Default")
      (node (ref "R3") (pin "1") (pinfunction "1_1") (pintype "passive"))
      (node (ref "U5") (pin "47") (pinfunction "USB_DP_47") (pintype "passive"))
    )
    (net (code "65") (name "Net-(X1-OSC2)") (class "Default")
      (node (ref "C25") (pin "2") (pinfunction "2_2") (pintype "passive"))
      (node (ref "R10") (pin "2") (pinfunction "2_2") (pintype "passive"))
      (node (ref "X1") (pin "3") (pinfunction "OSC2_3") (pintype "passive"))
    )
    (net (code "66") (name "unconnected-(U4-DO-Pad1)") (class "Default")
      (node (ref "U4") (pin "1") (pinfunction "DO_1") (pintype "passive"))
    )
  )
)
